# 26_LMS3_RX2_BB_ADC.net
KiCad netlist of a schematic drawn in Altium Designer
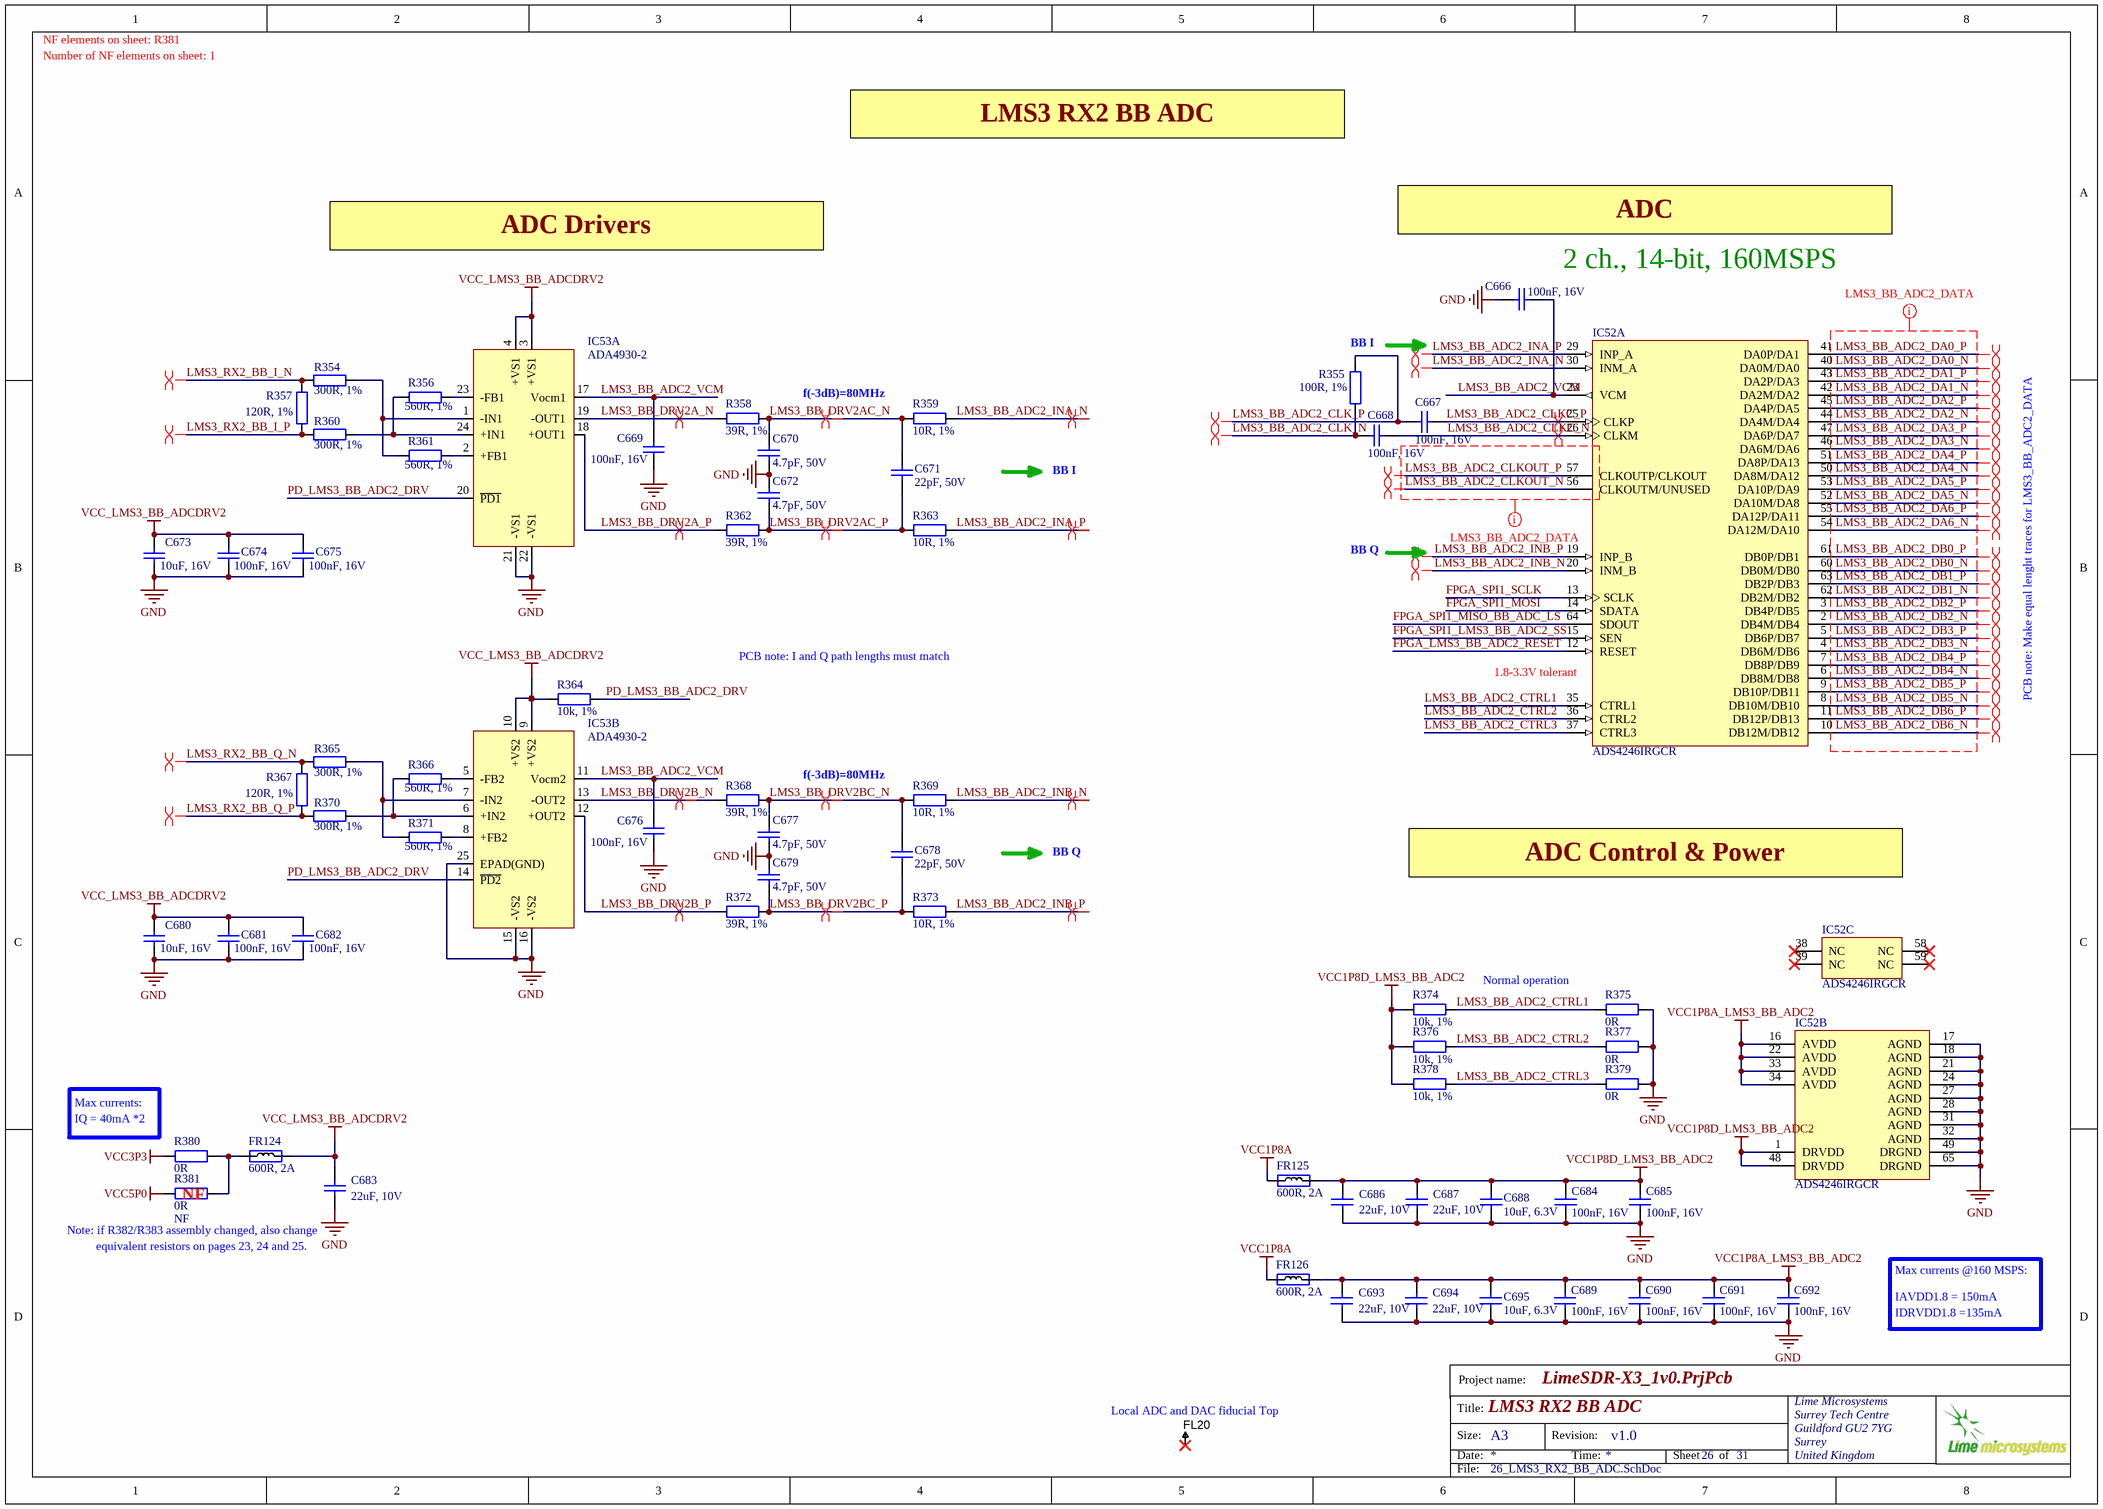
[diagram p0: 26_LMS3_RX2_BB_ADC.SchDoc]

(export (version "E")
  (design (tool "Eeschema 10.0.6"))
  (components
    (comp (ref "C666")
      (value "100nF, 16V")
      (footprint "CAP0402")
      (fields (field (name "TOLERANCE") "10 %") (field (name "MANUFACTURER") "Murata Electronics"))
      (libsource (lib "") (part "Cap_0603_7"))
    )
    (comp (ref "C667")
      (value "100nF, 16V")
      (footprint "CAP0402")
      (fields (field (name "TOLERANCE") "10 %") (field (name "MANUFACTURER") "Murata Electronics"))
      (libsource (lib "") (part "Cap_0603_7"))
    )
    (comp (ref "C668")
      (value "100nF, 16V")
      (footprint "CAP0402")
      (fields (field (name "TOLERANCE") "10 %") (field (name "MANUFACTURER") "Murata Electronics"))
      (libsource (lib "") (part "Cap_0603_2"))
    )
    (comp (ref "C669")
      (value "100nF, 16V")
      (footprint "CAP0402")
      (fields (field (name "TOLERANCE") "10 %") (field (name "MANUFACTURER") "Murata Electronics"))
      (libsource (lib "") (part "Cap_0603_2"))
    )
    (comp (ref "C670")
      (value "4.7pF, 50V")
      (footprint "CAP0402")
      (fields (field (name "MANUFACTURER") "MURATA"))
      (libsource (lib "LimeMicroAltiumLib_schLib") (part "Cap_0402"))
    )
    (comp (ref "C671")
      (value "22pF, 50V")
      (footprint "CAP0402")
      (fields (field (name "TOLERANCE") "±5%") (field (name "MANUFACTURER") "Yageo"))
      (libsource (lib "") (part "Cap_0402_1"))
    )
    (comp (ref "C672")
      (value "4.7pF, 50V")
      (footprint "CAP0402")
      (fields (field (name "MANUFACTURER") "MURATA"))
      (libsource (lib "LimeMicroAltiumLib_schLib") (part "Cap_0402"))
    )
    (comp (ref "C673")
      (value "10uF, 16V")
      (footprint "CAP0603")
      (fields (field (name "MANUFACTURER") "Yageo") (field (name "TOLERANCE") "±20%"))
      (libsource (lib "LimeMicroAltiumLib_schLib") (part "Cap_0603"))
    )
    (comp (ref "C674")
      (value "100nF, 16V")
      (footprint "CAP0402")
      (fields (field (name "TOLERANCE") "10 %") (field (name "MANUFACTURER") "Murata Electronics"))
      (libsource (lib "") (part "Cap_0603_2"))
    )
    (comp (ref "C675")
      (value "100nF, 16V")
      (footprint "CAP0402")
      (fields (field (name "TOLERANCE") "10 %") (field (name "MANUFACTURER") "Murata Electronics"))
      (libsource (lib "") (part "Cap_0603_2"))
    )
    (comp (ref "C676")
      (value "100nF, 16V")
      (footprint "CAP0402")
      (fields (field (name "TOLERANCE") "10 %") (field (name "MANUFACTURER") "Murata Electronics"))
      (libsource (lib "") (part "Cap_0603_6"))
    )
    (comp (ref "C677")
      (value "4.7pF, 50V")
      (footprint "CAP0402")
      (fields (field (name "MANUFACTURER") "MURATA"))
      (libsource (lib "LimeMicroAltiumLib_schLib") (part "Cap_0402"))
    )
    (comp (ref "C678")
      (value "22pF, 50V")
      (footprint "CAP0402")
      (fields (field (name "TOLERANCE") "±5%") (field (name "MANUFACTURER") "Yageo"))
      (libsource (lib "") (part "Cap_0402_1"))
    )
    (comp (ref "C679")
      (value "4.7pF, 50V")
      (footprint "CAP0402")
      (fields (field (name "MANUFACTURER") "MURATA"))
      (libsource (lib "LimeMicroAltiumLib_schLib") (part "Cap_0402"))
    )
    (comp (ref "C680")
      (value "10uF, 16V")
      (footprint "CAP0603")
      (fields (field (name "MANUFACTURER") "Yageo") (field (name "TOLERANCE") "±20%"))
      (libsource (lib "LimeMicroAltiumLib_schLib") (part "Cap_0603"))
    )
    (comp (ref "C681")
      (value "100nF, 16V")
      (footprint "CAP0402")
      (fields (field (name "TOLERANCE") "10 %") (field (name "MANUFACTURER") "Murata Electronics"))
      (libsource (lib "") (part "Cap_0603_2"))
    )
    (comp (ref "C682")
      (value "100nF, 16V")
      (footprint "CAP0402")
      (fields (field (name "TOLERANCE") "10 %") (field (name "MANUFACTURER") "Murata Electronics"))
      (libsource (lib "") (part "Cap_0603_2"))
    )
    (comp (ref "C683")
      (value "22uF, 10V")
      (footprint "CAP0603")
      (fields (field (name "TOLERANCE") "20 %") (field (name "MANUFACTURER") "TDK Corporation"))
      (libsource (lib "") (part "Cap_0603_3"))
    )
    (comp (ref "C684")
      (value "100nF, 16V")
      (footprint "CAP0402")
      (fields (field (name "TOLERANCE") "10 %") (field (name "MANUFACTURER") "Murata Electronics"))
      (libsource (lib "") (part "Cap_0603_5"))
    )
    (comp (ref "C685")
      (value "100nF, 16V")
      (footprint "CAP0402")
      (fields (field (name "TOLERANCE") "10 %") (field (name "MANUFACTURER") "Murata Electronics"))
      (libsource (lib "") (part "Cap_0603_5"))
    )
    (comp (ref "C686")
      (value "22uF, 10V")
      (footprint "CAP0603")
      (fields (field (name "TOLERANCE") "20 %") (field (name "MANUFACTURER") "TDK Corporation"))
      (libsource (lib "") (part "Cap_0603_5"))
    )
    (comp (ref "C687")
      (value "22uF, 10V")
      (footprint "CAP0603")
      (fields (field (name "TOLERANCE") "20 %") (field (name "MANUFACTURER") "TDK Corporation"))
      (libsource (lib "") (part "Cap_0603_5"))
    )
    (comp (ref "C688")
      (value "10uF, 6.3V")
      (footprint "CAP0603")
      (fields (field (name "TOLERANCE") "±20%") (field (name "MANUFACTURER") "Yageo"))
      (libsource (lib "") (part "Cap_0603_1"))
    )
    (comp (ref "C689")
      (value "100nF, 16V")
      (footprint "CAP0402")
      (fields (field (name "TOLERANCE") "10 %") (field (name "MANUFACTURER") "Murata Electronics"))
      (libsource (lib "LimeFPGAboard_schLib") (part "Cap_0603"))
    )
    (comp (ref "C690")
      (value "100nF, 16V")
      (footprint "CAP0402")
      (fields (field (name "TOLERANCE") "10 %") (field (name "MANUFACTURER") "Murata Electronics"))
      (libsource (lib "LimeFPGAboard_schLib") (part "Cap_0603"))
    )
    (comp (ref "C691")
      (value "100nF, 16V")
      (footprint "CAP0402")
      (fields (field (name "TOLERANCE") "10 %") (field (name "MANUFACTURER") "Murata Electronics"))
      (libsource (lib "LimeFPGAboard_schLib") (part "Cap_0603"))
    )
    (comp (ref "C692")
      (value "100nF, 16V")
      (footprint "CAP0402")
      (fields (field (name "TOLERANCE") "10 %") (field (name "MANUFACTURER") "Murata Electronics"))
      (libsource (lib "LimeFPGAboard_schLib") (part "Cap_0603"))
    )
    (comp (ref "C693")
      (value "22uF, 10V")
      (footprint "CAP0603")
      (fields (field (name "TOLERANCE") "20 %") (field (name "MANUFACTURER") "TDK Corporation"))
      (libsource (lib "LimeFPGAboard_schLib") (part "Cap_0603"))
    )
    (comp (ref "C694")
      (value "22uF, 10V")
      (footprint "CAP0603")
      (fields (field (name "TOLERANCE") "20 %") (field (name "MANUFACTURER") "TDK Corporation"))
      (libsource (lib "LimeFPGAboard_schLib") (part "Cap_0603"))
    )
    (comp (ref "C695")
      (value "10uF, 6.3V")
      (footprint "CAP0603")
      (fields (field (name "TOLERANCE") "±20%") (field (name "MANUFACTURER") "Yageo"))
      (libsource (lib "") (part "Cap_0603_4"))
    )
    (comp (ref "FL20")
      (value "Fiducial")
      (footprint "Fiducial_local")
      (libsource (lib "LimeMicroAltiumLib_schLib") (part "Fiducial"))
    )
    (comp (ref "FR124")
      (value "600R, 2A")
      (footprint "RES0805")
      (fields (field (name "MANUFACTURER") "TDK Corporation"))
      (libsource (lib "LimeMicroAltiumLib_schLib") (part "Ferrite"))
    )
    (comp (ref "FR125")
      (value "600R, 2A")
      (footprint "RES0805")
      (fields (field (name "MANUFACTURER") "TDK Corporation"))
      (libsource (lib "LimeFPGAboard_schLib") (part "Ferrite"))
    )
    (comp (ref "FR126")
      (value "600R, 2A")
      (footprint "RES0805")
      (fields (field (name "MANUFACTURER") "TDK Corporation"))
      (libsource (lib "LimeFPGAboard_schLib") (part "Ferrite"))
    )
    (comp (ref "IC52")
      (value "ADS4246IRGCR")
      (footprint "TI-RGC64-7400X7400TP_V")
      (description "14-Bit 160 MSPS Dual Low Power ADC, -40 to 85 degC, 64-pin QFN (RGC64), Green (RoHS & no Sb/Br)")
      (fields (field (name "MANUFACTURER") "Texas Instruments"))
      (libsource (lib "") (part "ADS4246IRGCR_1"))
    )
    (comp (ref "IC53")
      (value "ADA4930-2")
      (footprint "ADA4930-2_LFCSP-24")
      (fields (field (name "MANUFACTURER") "Analog Devices Inc."))
      (libsource (lib "") (part "ADA4930-2_1"))
    )
    (comp (ref "R354")
      (value "300R, 1%")
      (footprint "RES0402")
      (fields (field (name "TOLERANCE") "±1%") (field (name "MANUFACTURER") "Vishay Dale"))
      (libsource (lib "LimeFPGAboard_schLib") (part "Res_0402"))
    )
    (comp (ref "R355")
      (value "100R, 1%")
      (footprint "RES0402")
      (fields (field (name "TOLERANCE") "±1%") (field (name "MANUFACTURER") "Stackpole Electronics Inc."))
      (libsource (lib "LimeFPGAboard_schLib") (part "Res_0402"))
    )
    (comp (ref "R356")
      (value "560R, 1%")
      (footprint "RES0402")
      (fields (field (name "TOLERANCE") "±1%") (field (name "MANUFACTURER") "Vishay Dale"))
      (libsource (lib "LimeFPGAboard_schLib") (part "Res_0402"))
    )
    (comp (ref "R357")
      (value "120R, 1%")
      (footprint "RES0402")
      (fields (field (name "MANUFACTURER") "Yageo") (field (name "TOLERANCE") "1%"))
      (libsource (lib "") (part "Res_0402_1"))
    )
    (comp (ref "R358")
      (value "39R, 1%")
      (footprint "RES0402")
      (fields (field (name "MANUFACTURER") "Yageo") (field (name "TOLERANCE") "1%"))
      (libsource (lib "LimeMicroAltiumLib_schLib") (part "Res_0402"))
    )
    (comp (ref "R359")
      (value "10R, 1%")
      (footprint "RES0402")
      (fields (field (name "TOLERANCE") "1%"))
      (libsource (lib "LimeMicroAltiumLib_schLib") (part "Res_0402"))
    )
    (comp (ref "R360")
      (value "300R, 1%")
      (footprint "RES0402")
      (fields (field (name "TOLERANCE") "±1%") (field (name "MANUFACTURER") "Vishay Dale"))
      (libsource (lib "LimeFPGAboard_schLib") (part "Res_0402"))
    )
    (comp (ref "R361")
      (value "560R, 1%")
      (footprint "RES0402")
      (fields (field (name "TOLERANCE") "±1%") (field (name "MANUFACTURER") "Vishay Dale"))
      (libsource (lib "LimeFPGAboard_schLib") (part "Res_0402"))
    )
    (comp (ref "R362")
      (value "39R, 1%")
      (footprint "RES0402")
      (fields (field (name "MANUFACTURER") "Yageo") (field (name "TOLERANCE") "1%"))
      (libsource (lib "LimeMicroAltiumLib_schLib") (part "Res_0402"))
    )
    (comp (ref "R363")
      (value "10R, 1%")
      (footprint "RES0402")
      (fields (field (name "TOLERANCE") "1%"))
      (libsource (lib "LimeMicroAltiumLib_schLib") (part "Res_0402"))
    )
    (comp (ref "R364")
      (value "10k, 1%")
      (footprint "RES0402")
      (fields (field (name "MANUFACTURER") "Yageo") (field (name "TOLERANCE") "±1%"))
      (libsource (lib "LimeMicroAltiumLib_schLib") (part "Res_0402"))
    )
    (comp (ref "R365")
      (value "300R, 1%")
      (footprint "RES0402")
      (fields (field (name "TOLERANCE") "±1%") (field (name "MANUFACTURER") "Vishay Dale"))
      (libsource (lib "LimeFPGAboard_schLib") (part "Res_0402"))
    )
    (comp (ref "R366")
      (value "560R, 1%")
      (footprint "RES0402")
      (fields (field (name "TOLERANCE") "±1%") (field (name "MANUFACTURER") "Vishay Dale"))
      (libsource (lib "LimeFPGAboard_schLib") (part "Res_0402"))
    )
    (comp (ref "R367")
      (value "120R, 1%")
      (footprint "RES0402")
      (fields (field (name "MANUFACTURER") "Yageo") (field (name "TOLERANCE") "1%"))
      (libsource (lib "") (part "Res_0402_1"))
    )
    (comp (ref "R368")
      (value "39R, 1%")
      (footprint "RES0402")
      (fields (field (name "MANUFACTURER") "Yageo") (field (name "TOLERANCE") "1%"))
      (libsource (lib "LimeMicroAltiumLib_schLib") (part "Res_0402"))
    )
    (comp (ref "R369")
      (value "10R, 1%")
      (footprint "RES0402")
      (fields (field (name "TOLERANCE") "1%"))
      (libsource (lib "LimeMicroAltiumLib_schLib") (part "Res_0402"))
    )
    (comp (ref "R370")
      (value "300R, 1%")
      (footprint "RES0402")
      (fields (field (name "TOLERANCE") "±1%") (field (name "MANUFACTURER") "Vishay Dale"))
      (libsource (lib "LimeFPGAboard_schLib") (part "Res_0402"))
    )
    (comp (ref "R371")
      (value "560R, 1%")
      (footprint "RES0402")
      (fields (field (name "TOLERANCE") "±1%") (field (name "MANUFACTURER") "Vishay Dale"))
      (libsource (lib "LimeFPGAboard_schLib") (part "Res_0402"))
    )
    (comp (ref "R372")
      (value "39R, 1%")
      (footprint "RES0402")
      (fields (field (name "MANUFACTURER") "Yageo") (field (name "TOLERANCE") "1%"))
      (libsource (lib "LimeMicroAltiumLib_schLib") (part "Res_0402"))
    )
    (comp (ref "R373")
      (value "10R, 1%")
      (footprint "RES0402")
      (fields (field (name "TOLERANCE") "1%"))
      (libsource (lib "LimeMicroAltiumLib_schLib") (part "Res_0402"))
    )
    (comp (ref "R374")
      (value "10k, 1%")
      (footprint "RES0402")
      (fields (field (name "MANUFACTURER") "Yageo") (field (name "TOLERANCE") "±1%"))
      (libsource (lib "LimeMicroAltiumLib_schLib") (part "Res_0402"))
    )
    (comp (ref "R375")
      (value "0R")
      (footprint "RES0402")
      (fields (field (name "MANUFACTURER") "Yageo"))
      (libsource (lib "LimeFPGAboard_schLib") (part "Res_0402"))
    )
    (comp (ref "R376")
      (value "10k, 1%")
      (footprint "RES0402")
      (fields (field (name "MANUFACTURER") "Yageo") (field (name "TOLERANCE") "±1%"))
      (libsource (lib "LimeMicroAltiumLib_schLib") (part "Res_0402"))
    )
    (comp (ref "R377")
      (value "0R")
      (footprint "RES0402")
      (fields (field (name "MANUFACTURER") "Yageo"))
      (libsource (lib "LimeFPGAboard_schLib") (part "Res_0402"))
    )
    (comp (ref "R378")
      (value "10k, 1%")
      (footprint "RES0402")
      (fields (field (name "MANUFACTURER") "Yageo") (field (name "TOLERANCE") "±1%"))
      (libsource (lib "LimeMicroAltiumLib_schLib") (part "Res_0402"))
    )
    (comp (ref "R379")
      (value "0R")
      (footprint "RES0402")
      (fields (field (name "MANUFACTURER") "Yageo"))
      (libsource (lib "LimeFPGAboard_schLib") (part "Res_0402"))
    )
    (comp (ref "R380")
      (value "0R")
      (footprint "RES0402")
      (fields (field (name "MANUFACTURER") "Yageo") (field (name "TOLERANCE") "Jumper"))
      (libsource (lib "LimeMicroAltiumLib_schLib") (part "Res_0402"))
    )
    (comp (ref "R381")
      (value "0R")
      (footprint "RES0402")
      (fields
        (field (name "ASSEMBLY INFO") "NF")
        (field (name "MANUFACTURER") "Yageo")
        (field (name "TOLERANCE") "Jumper")
      )
      (libsource (lib "LimeMicroAltiumLib_schLib") (part "Res_0402"))
    )
  )
  (nets
    (net (code "1") (name "/FPGA_LMS3_BB_ADC2_RESET") (class "Default")
      (node (ref "IC52") (pin "12") (pinfunction "RESET_12") (pintype "input"))
    )
    (net (code "2") (name "/FPGA_SPI1_LMS3_BB_ADC2_SS") (class "Default")
      (node (ref "IC52") (pin "15") (pinfunction "SEN_15") (pintype "input"))
    )
    (net (code "3") (name "/FPGA_SPI1_MISO_BB_ADC_LS") (class "Default")
      (node (ref "IC52") (pin "64") (pinfunction "SDOUT_64") (pintype "tri_state"))
    )
    (net (code "4") (name "/FPGA_SPI1_MOSI") (class "Default")
      (node (ref "IC52") (pin "14") (pinfunction "SDATA_14") (pintype "input"))
    )
    (net (code "5") (name "/FPGA_SPI1_SCLK") (class "Default")
      (node (ref "IC52") (pin "13") (pinfunction "SCLK_13") (pintype "input"))
    )
    (net (code "6") (name "/LMS3_BB_ADC2_CLKC_N") (class "Default")
      (node (ref "C668") (pin "1") (pinfunction "1_1") (pintype "passive"))
      (node (ref "IC52") (pin "26") (pinfunction "CLKM_26") (pintype "input"))
    )
    (net (code "7") (name "/LMS3_BB_ADC2_CLKC_P") (class "Default")
      (node (ref "C667") (pin "1") (pinfunction "1_1") (pintype "passive"))
      (node (ref "IC52") (pin "25") (pinfunction "CLKP_25") (pintype "input"))
    )
    (net (code "8") (name "/LMS3_BB_ADC2_CLKOUT_N") (class "Default")
      (node (ref "IC52") (pin "56") (pinfunction "CLKOUTM/UNUSED_56") (pintype "tri_state"))
    )
    (net (code "9") (name "/LMS3_BB_ADC2_CLKOUT_P") (class "Default")
      (node (ref "IC52") (pin "57") (pinfunction "CLKOUTP/CLKOUT_57") (pintype "tri_state"))
    )
    (net (code "10") (name "/LMS3_BB_ADC2_CLK_N") (class "Default")
      (node (ref "C668") (pin "2") (pinfunction "2_2") (pintype "passive"))
      (node (ref "R355") (pin "1") (pinfunction "1_1") (pintype "passive"))
    )
    (net (code "11") (name "/LMS3_BB_ADC2_CLK_P") (class "Default")
      (node (ref "C667") (pin "2") (pinfunction "2_2") (pintype "passive"))
      (node (ref "R355") (pin "2") (pinfunction "2_2") (pintype "passive"))
    )
    (net (code "12") (name "/LMS3_BB_ADC2_CTRL1") (class "Default")
      (node (ref "IC52") (pin "35") (pinfunction "CTRL1_35") (pintype "input"))
      (node (ref "R374") (pin "1") (pinfunction "1_1") (pintype "passive"))
      (node (ref "R375") (pin "2") (pinfunction "2_2") (pintype "passive"))
    )
    (net (code "13") (name "/LMS3_BB_ADC2_CTRL2") (class "Default")
      (node (ref "IC52") (pin "36") (pinfunction "CTRL2_36") (pintype "input"))
      (node (ref "R376") (pin "1") (pinfunction "1_1") (pintype "passive"))
      (node (ref "R377") (pin "2") (pinfunction "2_2") (pintype "passive"))
    )
    (net (code "14") (name "/LMS3_BB_ADC2_CTRL3") (class "Default")
      (node (ref "IC52") (pin "37") (pinfunction "CTRL3_37") (pintype "input"))
      (node (ref "R378") (pin "1") (pinfunction "1_1") (pintype "passive"))
      (node (ref "R379") (pin "2") (pinfunction "2_2") (pintype "passive"))
    )
    (net (code "15") (name "/LMS3_BB_ADC2_DA0_N") (class "Default")
      (node (ref "IC52") (pin "40") (pinfunction "DA0M/DA0_40") (pintype "tri_state"))
    )
    (net (code "16") (name "/LMS3_BB_ADC2_DA0_P") (class "Default")
      (node (ref "IC52") (pin "41") (pinfunction "DA0P/DA1_41") (pintype "tri_state"))
    )
    (net (code "17") (name "/LMS3_BB_ADC2_DA1_N") (class "Default")
      (node (ref "IC52") (pin "42") (pinfunction "DA2M/DA2_42") (pintype "tri_state"))
    )
    (net (code "18") (name "/LMS3_BB_ADC2_DA1_P") (class "Default")
      (node (ref "IC52") (pin "43") (pinfunction "DA2P/DA3_43") (pintype "tri_state"))
    )
    (net (code "19") (name "/LMS3_BB_ADC2_DA2_N") (class "Default")
      (node (ref "IC52") (pin "44") (pinfunction "DA4M/DA4_44") (pintype "tri_state"))
    )
    (net (code "20") (name "/LMS3_BB_ADC2_DA2_P") (class "Default")
      (node (ref "IC52") (pin "45") (pinfunction "DA4P/DA5_45") (pintype "tri_state"))
    )
    (net (code "21") (name "/LMS3_BB_ADC2_DA3_N") (class "Default")
      (node (ref "IC52") (pin "46") (pinfunction "DA6M/DA6_46") (pintype "tri_state"))
    )
    (net (code "22") (name "/LMS3_BB_ADC2_DA3_P") (class "Default")
      (node (ref "IC52") (pin "47") (pinfunction "DA6P/DA7_47") (pintype "tri_state"))
    )
    (net (code "23") (name "/LMS3_BB_ADC2_DA4_N") (class "Default")
      (node (ref "IC52") (pin "50") (pinfunction "DA8M/DA12_50") (pintype "tri_state"))
    )
    (net (code "24") (name "/LMS3_BB_ADC2_DA4_P") (class "Default")
      (node (ref "IC52") (pin "51") (pinfunction "DA8P/DA13_51") (pintype "tri_state"))
    )
    (net (code "25") (name "/LMS3_BB_ADC2_DA5_N") (class "Default")
      (node (ref "IC52") (pin "52") (pinfunction "DA10M/DA8_52") (pintype "tri_state"))
    )
    (net (code "26") (name "/LMS3_BB_ADC2_DA5_P") (class "Default")
      (node (ref "IC52") (pin "53") (pinfunction "DA10P/DA9_53") (pintype "tri_state"))
    )
    (net (code "27") (name "/LMS3_BB_ADC2_DA6_N") (class "Default")
      (node (ref "IC52") (pin "54") (pinfunction "DA12M/DA10_54") (pintype "tri_state"))
    )
    (net (code "28") (name "/LMS3_BB_ADC2_DA6_P") (class "Default")
      (node (ref "IC52") (pin "55") (pinfunction "DA12P/DA11_55") (pintype "tri_state"))
    )
    (net (code "29") (name "/LMS3_BB_ADC2_DB0_N") (class "Default")
      (node (ref "IC52") (pin "60") (pinfunction "DB0M/DB0_60") (pintype "tri_state"))
    )
    (net (code "30") (name "/LMS3_BB_ADC2_DB0_P") (class "Default")
      (node (ref "IC52") (pin "61") (pinfunction "DB0P/DB1_61") (pintype "tri_state"))
    )
    (net (code "31") (name "/LMS3_BB_ADC2_DB1_N") (class "Default")
      (node (ref "IC52") (pin "62") (pinfunction "DB2M/DB2_62") (pintype "tri_state"))
    )
    (net (code "32") (name "/LMS3_BB_ADC2_DB1_P") (class "Default")
      (node (ref "IC52") (pin "63") (pinfunction "DB2P/DB3_63") (pintype "tri_state"))
    )
    (net (code "33") (name "/LMS3_BB_ADC2_DB2_N") (class "Default")
      (node (ref "IC52") (pin "2") (pinfunction "DB4M/DB4_2") (pintype "tri_state"))
    )
    (net (code "34") (name "/LMS3_BB_ADC2_DB2_P") (class "Default")
      (node (ref "IC52") (pin "3") (pinfunction "DB4P/DB5_3") (pintype "tri_state"))
    )
    (net (code "35") (name "/LMS3_BB_ADC2_DB3_N") (class "Default")
      (node (ref "IC52") (pin "4") (pinfunction "DB6M/DB6_4") (pintype "tri_state"))
    )
    (net (code "36") (name "/LMS3_BB_ADC2_DB3_P") (class "Default")
      (node (ref "IC52") (pin "5") (pinfunction "DB6P/DB7_5") (pintype "tri_state"))
    )
    (net (code "37") (name "/LMS3_BB_ADC2_DB4_N") (class "Default")
      (node (ref "IC52") (pin "6") (pinfunction "DB8M/DB8_6") (pintype "tri_state"))
    )
    (net (code "38") (name "/LMS3_BB_ADC2_DB4_P") (class "Default")
      (node (ref "IC52") (pin "7") (pinfunction "DB8P/DB9_7") (pintype "tri_state"))
    )
    (net (code "39") (name "/LMS3_BB_ADC2_DB5_N") (class "Default")
      (node (ref "IC52") (pin "8") (pinfunction "DB10M/DB10_8") (pintype "tri_state"))
    )
    (net (code "40") (name "/LMS3_BB_ADC2_DB5_P") (class "Default")
      (node (ref "IC52") (pin "9") (pinfunction "DB10P/DB11_9") (pintype "tri_state"))
    )
    (net (code "41") (name "/LMS3_BB_ADC2_DB6_N") (class "Default")
      (node (ref "IC52") (pin "10") (pinfunction "DB12M/DB12_10") (pintype "tri_state"))
    )
    (net (code "42") (name "/LMS3_BB_ADC2_DB6_P") (class "Default")
      (node (ref "IC52") (pin "11") (pinfunction "DB12P/DB13_11") (pintype "tri_state"))
    )
    (net (code "43") (name "/LMS3_BB_ADC2_INA_N") (class "Default")
      (node (ref "IC52") (pin "30") (pinfunction "INM_A_30") (pintype "input"))
      (node (ref "R359") (pin "1") (pinfunction "1_1") (pintype "passive"))
    )
    (net (code "44") (name "/LMS3_BB_ADC2_INA_P") (class "Default")
      (node (ref "IC52") (pin "29") (pinfunction "INP_A_29") (pintype "input"))
      (node (ref "R363") (pin "1") (pinfunction "1_1") (pintype "passive"))
    )
    (net (code "45") (name "/LMS3_BB_ADC2_INB_N") (class "Default")
      (node (ref "IC52") (pin "20") (pinfunction "INM_B_20") (pintype "input"))
      (node (ref "R369") (pin "1") (pinfunction "1_1") (pintype "passive"))
    )
    (net (code "46") (name "/LMS3_BB_ADC2_INB_P") (class "Default")
      (node (ref "IC52") (pin "19") (pinfunction "INP_B_19") (pintype "input"))
      (node (ref "R373") (pin "1") (pinfunction "1_1") (pintype "passive"))
    )
    (net (code "47") (name "/LMS3_BB_ADC2_VCM") (class "Default")
      (node (ref "C666") (pin "2") (pinfunction "2_2") (pintype "passive"))
      (node (ref "C669") (pin "1") (pinfunction "1_1") (pintype "passive"))
      (node (ref "C676") (pin "1") (pinfunction "1_1") (pintype "passive"))
      (node (ref "IC52") (pin "23") (pinfunction "VCM_23") (pintype "output"))
      (node (ref "IC53") (pin "11") (pinfunction "Vocm2_11") (pintype "input"))
      (node (ref "IC53") (pin "17") (pinfunction "Vocm1_17") (pintype "input"))
    )
    (net (code "48") (name "/LMS3_BB_DRV2AC_N") (class "Default")
      (node (ref "C670") (pin "1") (pinfunction "1_1") (pintype "passive"))
      (node (ref "C671") (pin "1") (pinfunction "1_1") (pintype "passive"))
      (node (ref "R358") (pin "1") (pinfunction "1_1") (pintype "passive"))
      (node (ref "R359") (pin "2") (pinfunction "2_2") (pintype "passive"))
    )
    (net (code "49") (name "/LMS3_BB_DRV2AC_P") (class "Default")
      (node (ref "C671") (pin "2") (pinfunction "2_2") (pintype "passive"))
      (node (ref "C672") (pin "2") (pinfunction "2_2") (pintype "passive"))
      (node (ref "R362") (pin "1") (pinfunction "1_1") (pintype "passive"))
      (node (ref "R363") (pin "2") (pinfunction "2_2") (pintype "passive"))
    )
    (net (code "50") (name "/LMS3_BB_DRV2A_N") (class "Default")
      (node (ref "IC53") (pin "19") (pinfunction "-OUT1_19") (pintype "output"))
      (node (ref "R358") (pin "2") (pinfunction "2_2") (pintype "passive"))
    )
    (net (code "51") (name "/LMS3_BB_DRV2A_P") (class "Default")
      (node (ref "IC53") (pin "18") (pinfunction "+OUT1_18") (pintype "output"))
      (node (ref "R362") (pin "2") (pinfunction "2_2") (pintype "passive"))
    )
    (net (code "52") (name "/LMS3_BB_DRV2BC_N") (class "Default")
      (node (ref "C677") (pin "1") (pinfunction "1_1") (pintype "passive"))
      (node (ref "C678") (pin "1") (pinfunction "1_1") (pintype "passive"))
      (node (ref "R368") (pin "1") (pinfunction "1_1") (pintype "passive"))
      (node (ref "R369") (pin "2") (pinfunction "2_2") (pintype "passive"))
    )
    (net (code "53") (name "/LMS3_BB_DRV2BC_P") (class "Default")
      (node (ref "C678") (pin "2") (pinfunction "2_2") (pintype "passive"))
      (node (ref "C679") (pin "2") (pinfunction "2_2") (pintype "passive"))
      (node (ref "R372") (pin "1") (pinfunction "1_1") (pintype "passive"))
      (node (ref "R373") (pin "2") (pinfunction "2_2") (pintype "passive"))
    )
    (net (code "54") (name "/LMS3_BB_DRV2B_N") (class "Default")
      (node (ref "IC53") (pin "13") (pinfunction "-OUT2_13") (pintype "output"))
      (node (ref "R368") (pin "2") (pinfunction "2_2") (pintype "passive"))
    )
    (net (code "55") (name "/LMS3_BB_DRV2B_P") (class "Default")
      (node (ref "IC53") (pin "12") (pinfunction "+OUT2_12") (pintype "output"))
      (node (ref "R372") (pin "2") (pinfunction "2_2") (pintype "passive"))
    )
    (net (code "56") (name "/LMS3_RX2_BB_I_N") (class "Default")
      (node (ref "R354") (pin "2") (pinfunction "2_2") (pintype "passive"))
      (node (ref "R357") (pin "2") (pinfunction "2_2") (pintype "passive"))
    )
    (net (code "57") (name "/LMS3_RX2_BB_I_P") (class "Default")
      (node (ref "R357") (pin "1") (pinfunction "1_1") (pintype "passive"))
      (node (ref "R360") (pin "2") (pinfunction "2_2") (pintype "passive"))
    )
    (net (code "58") (name "/LMS3_RX2_BB_Q_N") (class "Default")
      (node (ref "R365") (pin "2") (pinfunction "2_2") (pintype "passive"))
      (node (ref "R367") (pin "2") (pinfunction "2_2") (pintype "passive"))
    )
    (net (code "59") (name "/LMS3_RX2_BB_Q_P") (class "Default")
      (node (ref "R367") (pin "1") (pinfunction "1_1") (pintype "passive"))
      (node (ref "R370") (pin "2") (pinfunction "2_2") (pintype "passive"))
    )
    (net (code "60") (name "/PD_LMS3_BB_ADC2_DRV") (class "Default")
      (node (ref "IC53") (pin "14") (pinfunction "~{PD2}_14") (pintype "input"))
      (node (ref "IC53") (pin "20") (pinfunction "~{PD1}_20") (pintype "input"))
      (node (ref "R364") (pin "1") (pinfunction "1_1") (pintype "passive"))
    )
    (net (code "61") (name "GND") (class "Default")
      (node (ref "C666") (pin "1") (pinfunction "1_1") (pintype "passive"))
      (node (ref "C669") (pin "2") (pinfunction "2_2") (pintype "passive"))
      (node (ref "C670") (pin "2") (pinfunction "2_2") (pintype "passive"))
      (node (ref "C672") (pin "1") (pinfunction "1_1") (pintype "passive"))
      (node (ref "C673") (pin "1") (pinfunction "1_1") (pintype "passive"))
      (node (ref "C674") (pin "2") (pinfunction "2_2") (pintype "passive"))
      (node (ref "C675") (pin "2") (pinfunction "2_2") (pintype "passive"))
      (node (ref "C676") (pin "2") (pinfunction "2_2") (pintype "passive"))
      (node (ref "C677") (pin "2") (pinfunction "2_2") (pintype "passive"))
      (node (ref "C679") (pin "1") (pinfunction "1_1") (pintype "passive"))
      (node (ref "C680") (pin "1") (pinfunction "1_1") (pintype "passive"))
      (node (ref "C681") (pin "2") (pinfunction "2_2") (pintype "passive"))
      (node (ref "C682") (pin "2") (pinfunction "2_2") (pintype "passive"))
      (node (ref "C683") (pin "1") (pinfunction "1_1") (pintype "passive"))
      (node (ref "C684") (pin "1") (pinfunction "1_1") (pintype "passive"))
      (node (ref "C685") (pin "1") (pinfunction "1_1") (pintype "passive"))
      (node (ref "C686") (pin "1") (pinfunction "1_1") (pintype "passive"))
      (node (ref "C687") (pin "1") (pinfunction "1_1") (pintype "passive"))
      (node (ref "C688") (pin "2") (pinfunction "2_2") (pintype "passive"))
      (node (ref "C689") (pin "1") (pinfunction "1_1") (pintype "passive"))
      (node (ref "C690") (pin "1") (pinfunction "1_1") (pintype "passive"))
      (node (ref "C691") (pin "1") (pinfunction "1_1") (pintype "passive"))
      (node (ref "C692") (pin "1") (pinfunction "1_1") (pintype "passive"))
      (node (ref "C693") (pin "1") (pinfunction "1_1") (pintype "passive"))
      (node (ref "C694") (pin "1") (pinfunction "1_1") (pintype "passive"))
      (node (ref "C695") (pin "2") (pinfunction "2_2") (pintype "passive"))
      (node (ref "IC52") (pin "17") (pinfunction "AGND_17") (pintype "power_in"))
      (node (ref "IC52") (pin "18") (pinfunction "AGND_18") (pintype "power_in"))
      (node (ref "IC52") (pin "21") (pinfunction "AGND_21") (pintype "power_in"))
      (node (ref "IC52") (pin "24") (pinfunction "AGND_24") (pintype "power_in"))
      (node (ref "IC52") (pin "27") (pinfunction "AGND_27") (pintype "power_in"))
      (node (ref "IC52") (pin "28") (pinfunction "AGND_28") (pintype "power_in"))
      (node (ref "IC52") (pin "31") (pinfunction "AGND_31") (pintype "power_in"))
      (node (ref "IC52") (pin "32") (pinfunction "AGND_32") (pintype "power_in"))
      (node (ref "IC52") (pin "49") (pinfunction "DRGND_49") (pintype "power_in"))
      (node (ref "IC52") (pin "65") (pinfunction "DRGND_65") (pintype "power_in"))
      (node (ref "IC53") (pin "15") (pinfunction "-VS2_15") (pintype "power_in"))
      (node (ref "IC53") (pin "16") (pinfunction "-VS2_16") (pintype "power_in"))
      (node (ref "IC53") (pin "21") (pinfunction "-VS1_21") (pintype "power_in"))
      (node (ref "IC53") (pin "22") (pinfunction "-VS1_22") (pintype "power_in"))
      (node (ref "IC53") (pin "25") (pinfunction "EPAD(GND)_25") (pintype "passive"))
      (node (ref "R375") (pin "1") (pinfunction "1_1") (pintype "passive"))
      (node (ref "R377") (pin "1") (pinfunction "1_1") (pintype "passive"))
      (node (ref "R379") (pin "1") (pinfunction "1_1") (pintype "passive"))
    )
    (net (code "62") (name "Net-(FR124-Pad1)") (class "Default")
      (node (ref "FR124") (pin "1") (pinfunction "1_1") (pintype "passive"))
      (node (ref "R380") (pin "1") (pinfunction "1_1") (pintype "passive"))
      (node (ref "R381") (pin "1") (pinfunction "1_1") (pintype "passive"))
    )
    (net (code "63") (name "Net-(IC53A-+FB1)") (class "Default")
      (node (ref "IC53") (pin "2") (pinfunction "+FB1_2") (pintype "output"))
      (node (ref "R361") (pin "1") (pinfunction "1_1") (pintype "passive"))
    )
    (net (code "64") (name "Net-(IC53A-+IN1)") (class "Default")
      (node (ref "IC53") (pin "24") (pinfunction "+IN1_24") (pintype "input"))
      (node (ref "R356") (pin "2") (pinfunction "2_2") (pintype "passive"))
      (node (ref "R360") (pin "1") (pinfunction "1_1") (pintype "passive"))
    )
    (net (code "65") (name "Net-(IC53A--FB1)") (class "Default")
      (node (ref "IC53") (pin "23") (pinfunction "-FB1_23") (pintype "output"))
      (node (ref "R356") (pin "1") (pinfunction "1_1") (pintype "passive"))
    )
    (net (code "66") (name "Net-(IC53A--IN1)") (class "Default")
      (node (ref "IC53") (pin "1") (pinfunction "-IN1_1") (pintype "input"))
      (node (ref "R354") (pin "1") (pinfunction "1_1") (pintype "passive"))
      (node (ref "R361") (pin "2") (pinfunction "2_2") (pintype "passive"))
    )
    (net (code "67") (name "Net-(IC53B-+FB2)") (class "Default")
      (node (ref "IC53") (pin "8") (pinfunction "+FB2_8") (pintype "output"))
      (node (ref "R371") (pin "1") (pinfunction "1_1") (pintype "passive"))
    )
    (net (code "68") (name "Net-(IC53B-+IN2)") (class "Default")
      (node (ref "IC53") (pin "6") (pinfunction "+IN2_6") (pintype "input"))
      (node (ref "R366") (pin "2") (pinfunction "2_2") (pintype "passive"))
      (node (ref "R370") (pin "1") (pinfunction "1_1") (pintype "passive"))
    )
    (net (code "69") (name "Net-(IC53B--FB2)") (class "Default")
      (node (ref "IC53") (pin "5") (pinfunction "-FB2_5") (pintype "output"))
      (node (ref "R366") (pin "1") (pinfunction "1_1") (pintype "passive"))
    )
    (net (code "70") (name "Net-(IC53B--IN2)") (class "Default")
      (node (ref "IC53") (pin "7") (pinfunction "-IN2_7") (pintype "input"))
      (node (ref "R365") (pin "1") (pinfunction "1_1") (pintype "passive"))
      (node (ref "R371") (pin "2") (pinfunction "2_2") (pintype "passive"))
    )
    (net (code "71") (name "VCC1P8A") (class "Default")
      (node (ref "FR125") (pin "1") (pinfunction "1_1") (pintype "passive"))
      (node (ref "FR126") (pin "1") (pinfunction "1_1") (pintype "passive"))
    )
    (net (code "72") (name "VCC1P8A_LMS3_BB_ADC2") (class "Default")
      (node (ref "C689") (pin "2") (pinfunction "2_2") (pintype "passive"))
      (node (ref "C690") (pin "2") (pinfunction "2_2") (pintype "passive"))
      (node (ref "C691") (pin "2") (pinfunction "2_2") (pintype "passive"))
      (node (ref "C692") (pin "2") (pinfunction "2_2") (pintype "passive"))
      (node (ref "C693") (pin "2") (pinfunction "2_2") (pintype "passive"))
      (node (ref "C694") (pin "2") (pinfunction "2_2") (pintype "passive"))
      (node (ref "C695") (pin "1") (pinfunction "1_1") (pintype "passive"))
      (node (ref "FR126") (pin "2") (pinfunction "2_2") (pintype "passive"))
      (node (ref "IC52") (pin "16") (pinfunction "AVDD_16") (pintype "power_in"))
      (node (ref "IC52") (pin "22") (pinfunction "AVDD_22") (pintype "power_in"))
      (node (ref "IC52") (pin "33") (pinfunction "AVDD_33") (pintype "power_in"))
      (node (ref "IC52") (pin "34") (pinfunction "AVDD_34") (pintype "power_in"))
    )
    (net (code "73") (name "VCC1P8D_LMS3_BB_ADC2") (class "Default")
      (node (ref "C684") (pin "2") (pinfunction "2_2") (pintype "passive"))
      (node (ref "C685") (pin "2") (pinfunction "2_2") (pintype "passive"))
      (node (ref "C686") (pin "2") (pinfunction "2_2") (pintype "passive"))
      (node (ref "C687") (pin "2") (pinfunction "2_2") (pintype "passive"))
      (node (ref "C688") (pin "1") (pinfunction "1_1") (pintype "passive"))
      (node (ref "FR125") (pin "2") (pinfunction "2_2") (pintype "passive"))
      (node (ref "IC52") (pin "1") (pinfunction "DRVDD_1") (pintype "power_in"))
      (node (ref "IC52") (pin "48") (pinfunction "DRVDD_48") (pintype "power_in"))
      (node (ref "R374") (pin "2") (pinfunction "2_2") (pintype "passive"))
      (node (ref "R376") (pin "2") (pinfunction "2_2") (pintype "passive"))
      (node (ref "R378") (pin "2") (pinfunction "2_2") (pintype "passive"))
    )
    (net (code "74") (name "VCC3P3") (class "Default")
      (node (ref "R380") (pin "2") (pinfunction "2_2") (pintype "passive"))
    )
    (net (code "75") (name "VCC5P0") (class "Default")
      (node (ref "R381") (pin "2") (pinfunction "2_2") (pintype "passive"))
    )
    (net (code "76") (name "VCC_LMS3_BB_ADCDRV2") (class "Default")
      (node (ref "C673") (pin "2") (pinfunction "2_2") (pintype "passive"))
      (node (ref "C674") (pin "1") (pinfunction "1_1") (pintype "passive"))
      (node (ref "C675") (pin "1") (pinfunction "1_1") (pintype "passive"))
      (node (ref "C680") (pin "2") (pinfunction "2_2") (pintype "passive"))
      (node (ref "C681") (pin "1") (pinfunction "1_1") (pintype "passive"))
      (node (ref "C682") (pin "1") (pinfunction "1_1") (pintype "passive"))
      (node (ref "C683") (pin "2") (pinfunction "2_2") (pintype "passive"))
      (node (ref "FR124") (pin "2") (pinfunction "2_2") (pintype "passive"))
      (node (ref "IC53") (pin "10") (pinfunction "+VS2_10") (pintype "power_in"))
      (node (ref "IC53") (pin "3") (pinfunction "+VS1_3") (pintype "power_in"))
      (node (ref "IC53") (pin "4") (pinfunction "+VS1_4") (pintype "power_in"))
      (node (ref "IC53") (pin "9") (pinfunction "+VS2_9") (pintype "power_in"))
      (node (ref "R364") (pin "2") (pinfunction "2_2") (pintype "passive"))
    )
    (net (code "77") (name "unconnected-(FL20-Pad1)") (class "Default")
      (node (ref "FL20") (pin "1") (pintype "passive+no_connect"))
    )
    (net (code "78") (name "unconnected-(IC52C-NC-Pad38)") (class "Default")
      (node (ref "IC52") (pin "38") (pinfunction "NC_38") (pintype "passive+no_connect"))
    )
    (net (code "79") (name "unconnected-(IC52C-NC-Pad39)") (class "Default")
      (node (ref "IC52") (pin "39") (pinfunction "NC_39") (pintype "passive+no_connect"))
    )
    (net (code "80") (name "unconnected-(IC52C-NC-Pad58)") (class "Default")
      (node (ref "IC52") (pin "58") (pinfunction "NC_58") (pintype "passive+no_connect"))
    )
    (net (code "81") (name "unconnected-(IC52C-NC-Pad59)") (class "Default")
      (node (ref "IC52") (pin "59") (pinfunction "NC_59") (pintype "passive+no_connect"))
    )
  )
)
